# 03.net
KiCad netlist of a schematic drawn in Altium Designer
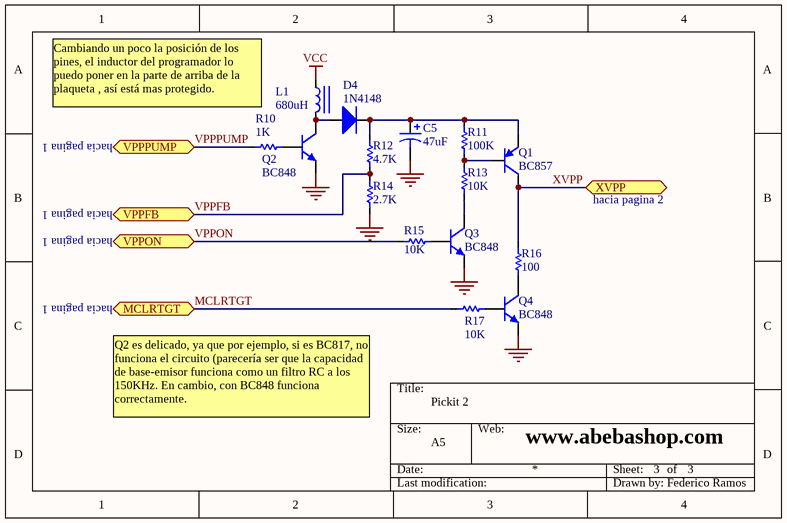
[diagram p0: 03.SchDoc]

(export (version "E")
  (design (tool "Eeschema 10.0.6"))
  (components
    (comp (ref "C5")
      (value "47uF")
      (footprint "D")
      (description "Solid Tantalum Chip Capacitor, Standard T491 Series - Industrial Grade")
      (fields (field (name "PUBLISHER") "Altium Limited"))
      (libsource (lib "KEMET Chip Capacitor") (part "T491D"))
    )
    (comp (ref "D4")
      (value "1N4148")
      (footprint "DSMD1MM")
      (description "High Conductance Fast Diode")
      (libsource (lib "FEDE") (part "1N4148"))
    )
    (comp (ref "L1")
      (value "680uH")
      (footprint "RES300TH")
      (description "Inductor")
      (libsource (lib "FEDE") (part "Inductor"))
    )
    (comp (ref "Q1")
      (value "BC857")
      (footprint "SOT23")
      (description "100mA 65V PNP Bipolar Transistor")
      (libsource (lib "FEDE") (part "BC856A"))
    )
    (comp (ref "Q2")
      (value "BC848")
      (footprint "SOT23")
      (description "100mA 65V NPN Bipolar Transistor")
      (libsource (lib "FEDE") (part "BC846A"))
    )
    (comp (ref "Q3")
      (value "BC848")
      (footprint "SOT23")
      (description "100mA 65V NPN Bipolar Transistor")
      (libsource (lib "FEDE") (part "BC846A"))
    )
    (comp (ref "Q4")
      (value "BC848")
      (footprint "SOT23")
      (description "100mA 65V NPN Bipolar Transistor")
      (libsource (lib "FEDE") (part "BC846A"))
    )
    (comp (ref "R10")
      (value "1K")
      (footprint "1206NP")
      (description "Resistor")
      (fields (field (name "POWER") "0.25W") (field (name "Comment") "Res"))
      (libsource (lib "FEDE") (part "Res"))
    )
    (comp (ref "R11")
      (value "100K")
      (footprint "1206NP")
      (description "Resistor")
      (fields (field (name "POWER") "0.25W") (field (name "Comment") "Res"))
      (libsource (lib "FEDE") (part "Res"))
    )
    (comp (ref "R12")
      (value "4.7K")
      (footprint "1206NP")
      (description "Resistor")
      (fields (field (name "POWER") "0.25W") (field (name "Comment") "Res"))
      (libsource (lib "FEDE") (part "Res"))
    )
    (comp (ref "R13")
      (value "10K")
      (footprint "1206NP")
      (description "Resistor")
      (fields (field (name "POWER") "0.25W") (field (name "Comment") "Res"))
      (libsource (lib "FEDE") (part "Res"))
    )
    (comp (ref "R14")
      (value "2.7K")
      (footprint "1206NP")
      (description "Resistor")
      (fields (field (name "POWER") "0.25W") (field (name "Comment") "Res"))
      (libsource (lib "FEDE") (part "Res"))
    )
    (comp (ref "R15")
      (value "10K")
      (footprint "1206NP")
      (description "Resistor")
      (fields (field (name "POWER") "0.25W") (field (name "Comment") "Res"))
      (libsource (lib "FEDE") (part "Res"))
    )
    (comp (ref "R16")
      (value "100")
      (footprint "1206NP")
      (description "Resistor")
      (fields (field (name "POWER") "0.25W") (field (name "Comment") "Res"))
      (libsource (lib "FEDE") (part "Res"))
    )
    (comp (ref "R17")
      (value "10K")
      (footprint "1206NP")
      (description "Resistor")
      (fields (field (name "POWER") "0.25W") (field (name "Comment") "Res"))
      (libsource (lib "FEDE") (part "Res"))
    )
  )
  (nets
    (net (code "1") (name "/MCLRTGT") (class "Default")
      (node (ref "R17") (pin "2") (pinfunction "2_2") (pintype "passive"))
    )
    (net (code "2") (name "/VPPFB") (class "Default")
      (node (ref "R12") (pin "1") (pinfunction "1_1") (pintype "passive"))
      (node (ref "R14") (pin "2") (pinfunction "2_2") (pintype "passive"))
    )
    (net (code "3") (name "/VPPON") (class "Default")
      (node (ref "R15") (pin "2") (pinfunction "2_2") (pintype "passive"))
    )
    (net (code "4") (name "/VPPPUMP") (class "Default")
      (node (ref "R10") (pin "2") (pinfunction "2_2") (pintype "passive"))
    )
    (net (code "5") (name "/XVPP") (class "Default")
      (node (ref "Q1") (pin "1") (pinfunction "C_1") (pintype "passive"))
      (node (ref "R16") (pin "2") (pinfunction "2_2") (pintype "passive"))
    )
    (net (code "6") (name "GND") (class "Default")
      (node (ref "C5") (pin "2") (pinfunction "2_2") (pintype "passive"))
      (node (ref "Q2") (pin "3") (pinfunction "E_3") (pintype "passive"))
      (node (ref "Q3") (pin "3") (pinfunction "E_3") (pintype "passive"))
      (node (ref "Q4") (pin "3") (pinfunction "E_3") (pintype "passive"))
      (node (ref "R14") (pin "1") (pinfunction "1_1") (pintype "passive"))
    )
    (net (code "7") (name "Net-(Q1-B)") (class "Default")
      (node (ref "Q1") (pin "2") (pinfunction "B_2") (pintype "passive"))
      (node (ref "R11") (pin "1") (pinfunction "1_1") (pintype "passive"))
      (node (ref "R13") (pin "2") (pinfunction "2_2") (pintype "passive"))
    )
    (net (code "8") (name "Net-(Q1-E)") (class "Default")
      (node (ref "C5") (pin "1") (pinfunction "1_1") (pintype "passive"))
      (node (ref "D4") (pin "2") (pinfunction "2_2") (pintype "passive"))
      (node (ref "Q1") (pin "3") (pinfunction "E_3") (pintype "passive"))
      (node (ref "R11") (pin "2") (pinfunction "2_2") (pintype "passive"))
      (node (ref "R12") (pin "2") (pinfunction "2_2") (pintype "passive"))
    )
    (net (code "9") (name "Net-(Q2-B)") (class "Default")
      (node (ref "Q2") (pin "2") (pinfunction "B_2") (pintype "passive"))
      (node (ref "R10") (pin "1") (pinfunction "1_1") (pintype "passive"))
    )
    (net (code "10") (name "Net-(Q2-C)") (class "Default")
      (node (ref "D4") (pin "1") (pinfunction "1_1") (pintype "passive"))
      (node (ref "L1") (pin "2") (pinfunction "2_2") (pintype "passive"))
      (node (ref "Q2") (pin "1") (pinfunction "C_1") (pintype "passive"))
    )
    (net (code "11") (name "Net-(Q3-B)") (class "Default")
      (node (ref "Q3") (pin "2") (pinfunction "B_2") (pintype "passive"))
      (node (ref "R15") (pin "1") (pinfunction "1_1") (pintype "passive"))
    )
    (net (code "12") (name "Net-(Q3-C)") (class "Default")
      (node (ref "Q3") (pin "1") (pinfunction "C_1") (pintype "passive"))
      (node (ref "R13") (pin "1") (pinfunction "1_1") (pintype "passive"))
    )
    (net (code "13") (name "Net-(Q4-B)") (class "Default")
      (node (ref "Q4") (pin "2") (pinfunction "B_2") (pintype "passive"))
      (node (ref "R17") (pin "1") (pinfunction "1_1") (pintype "passive"))
    )
    (net (code "14") (name "Net-(Q4-C)") (class "Default")
      (node (ref "Q4") (pin "1") (pinfunction "C_1") (pintype "passive"))
      (node (ref "R16") (pin "1") (pinfunction "1_1") (pintype "passive"))
    )
    (net (code "15") (name "VCC") (class "Default")
      (node (ref "L1") (pin "1") (pinfunction "1_1") (pintype "passive"))
    )
  )
)
